# MCU_Net.net
KiCad netlist of a schematic drawn in Altium Designer
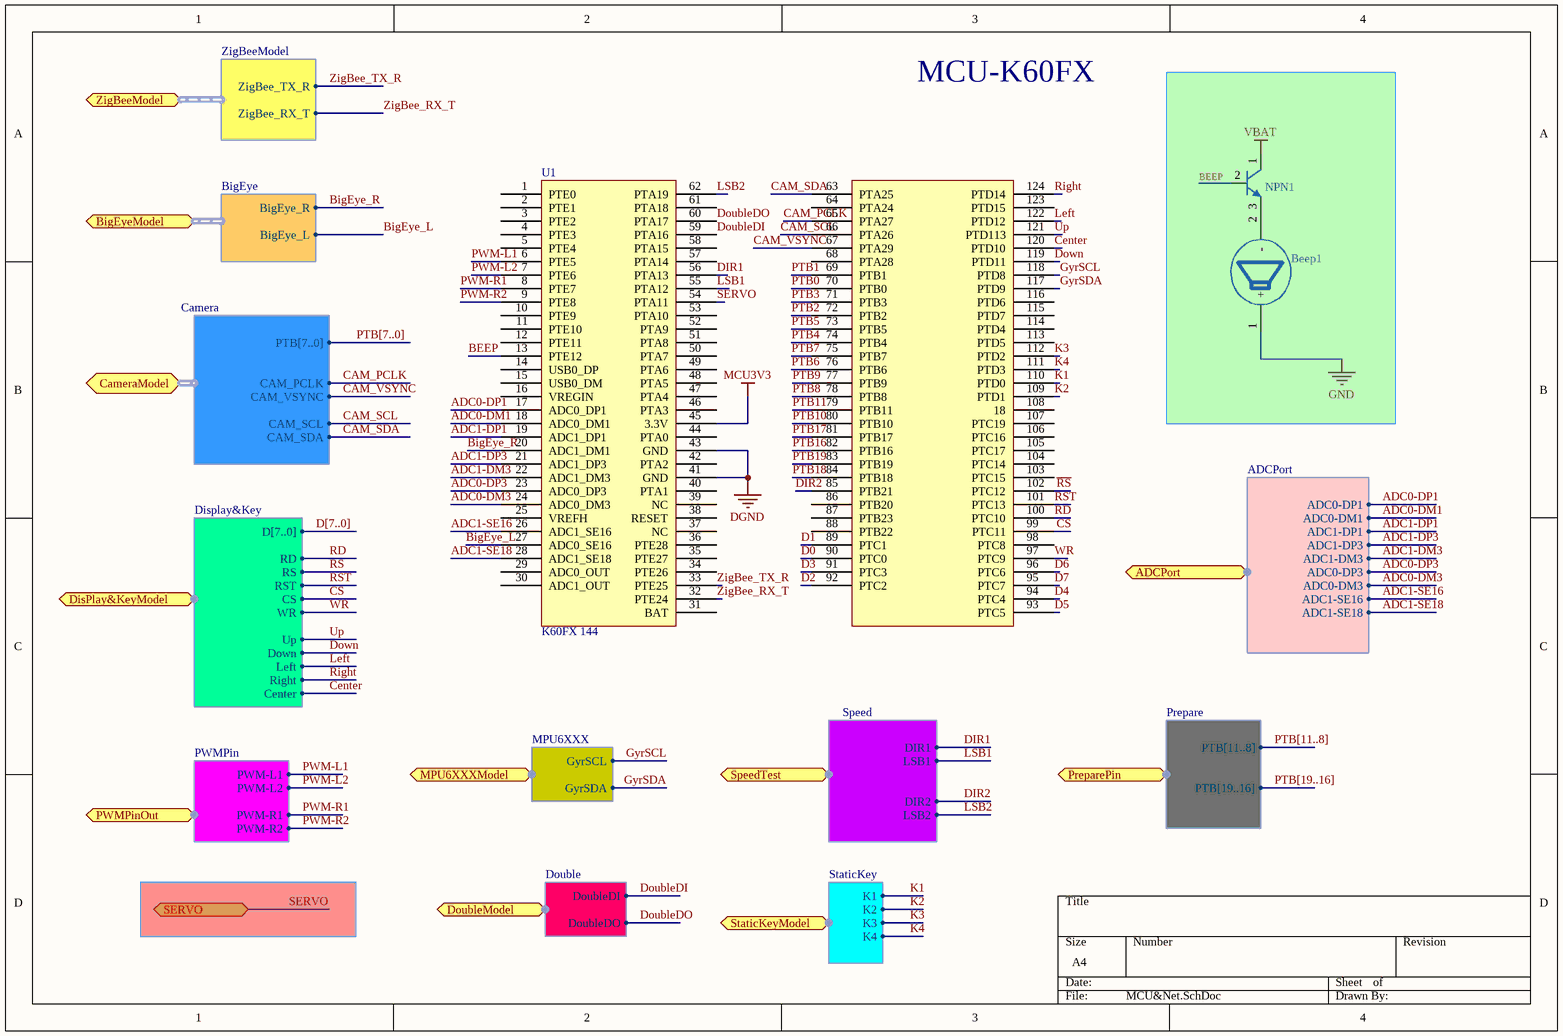
[diagram p0: MCU&Net.SchDoc]

(export (version "E")
  (design (tool "Eeschema 10.0.6"))
  (components
    (comp (ref "Beep1") (value "BEEP") (footprint "BEEP") (libsource (lib "常用原件库") (part "蜂鸣器")))
    (comp (ref "NPN1") (value "NPN") (footprint "三极管  NPN") (libsource (lib "常用原件库") (part "NPN")))
    (comp (ref "U1")
      (value "K60FX 144")
      (footprint "K60FX 144")
      (libsource (lib "常用原件库") (part "K60FX   144"))
    )
  )
  (nets
    (net (code "12") (name "/ADC0-DM1") (class "Default")
      (node (ref "U1") (pin "18") (pinfunction "ADC0_DM1_18") (pintype "passive"))
    )
    (net (code "13") (name "/ADC0-DM3") (class "Default")
      (node (ref "U1") (pin "24") (pinfunction "ADC0_DM3_24") (pintype "passive"))
    )
    (net (code "14") (name "/ADC0-DP1") (class "Default")
      (node (ref "U1") (pin "17") (pinfunction "ADC0_DP1_17") (pintype "passive"))
    )
    (net (code "15") (name "/ADC0-DP3") (class "Default")
      (node (ref "U1") (pin "23") (pinfunction "ADC0_DP3_23") (pintype "passive"))
    )
    (net (code "16") (name "/ADC1-DM3") (class "Default")
      (node (ref "U1") (pin "22") (pinfunction "ADC1_DM3_22") (pintype "passive"))
    )
    (net (code "17") (name "/ADC1-DP1") (class "Default")
      (node (ref "U1") (pin "19") (pinfunction "ADC1_DP1_19") (pintype "passive"))
    )
    (net (code "18") (name "/ADC1-DP3") (class "Default")
      (node (ref "U1") (pin "21") (pinfunction "ADC1_DP3_21") (pintype "passive"))
    )
    (net (code "19") (name "/ADC1-SE16") (class "Default")
      (node (ref "U1") (pin "26") (pinfunction "ADC1_SE16_26") (pintype "passive"))
    )
    (net (code "20") (name "/ADC1-SE18") (class "Default")
      (node (ref "U1") (pin "28") (pinfunction "ADC1_SE18_28") (pintype "passive"))
    )
    (net (code "21") (name "/BEEP") (class "Default")
      (node (ref "NPN1") (pin "2") (pinfunction "2_2") (pintype "passive"))
      (node (ref "U1") (pin "13") (pinfunction "PTE12_13") (pintype "passive"))
    )
    (net (code "22") (name "/BigEye_L") (class "Default")
      (node (ref "U1") (pin "27") (pinfunction "ADC0_SE16_27") (pintype "passive"))
    )
    (net (code "23") (name "/BigEye_R") (class "Default")
      (node (ref "U1") (pin "20") (pinfunction "ADC1_DM1_20") (pintype "passive"))
    )
    (net (code "24") (name "/CAM_PCLK") (class "Default")
      (node (ref "U1") (pin "65") (pinfunction "PTA27_65") (pintype "passive"))
    )
    (net (code "25") (name "/CAM_SCL") (class "Default")
      (node (ref "U1") (pin "66") (pinfunction "PTA26_66") (pintype "passive"))
    )
    (net (code "26") (name "/CAM_SDA") (class "Default")
      (node (ref "U1") (pin "63") (pinfunction "PTA25_63") (pintype "passive"))
    )
    (net (code "27") (name "/CAM_VSYNC") (class "Default")
      (node (ref "U1") (pin "67") (pinfunction "PTA29_67") (pintype "passive"))
    )
    (net (code "28") (name "/CS") (class "Default")
      (node (ref "U1") (pin "99") (pinfunction "PTC11_99") (pintype "passive"))
    )
    (net (code "29") (name "/Center") (class "Default")
      (node (ref "U1") (pin "120") (pinfunction "PTD10_120") (pintype "passive"))
    )
    (net (code "30") (name "/D0") (class "Default")
      (node (ref "U1") (pin "90") (pinfunction "PTC0_90") (pintype "passive"))
    )
    (net (code "31") (name "/D1") (class "Default")
      (node (ref "U1") (pin "89") (pinfunction "PTC1_89") (pintype "passive"))
    )
    (net (code "32") (name "/D2") (class "Default")
      (node (ref "U1") (pin "92") (pinfunction "PTC2_92") (pintype "passive"))
    )
    (net (code "33") (name "/D3") (class "Default")
      (node (ref "U1") (pin "91") (pinfunction "PTC3_91") (pintype "passive"))
    )
    (net (code "34") (name "/D4") (class "Default")
      (node (ref "U1") (pin "94") (pinfunction "PTC4_94") (pintype "passive"))
    )
    (net (code "35") (name "/D5") (class "Default")
      (node (ref "U1") (pin "93") (pinfunction "PTC5_93") (pintype "passive"))
    )
    (net (code "36") (name "/D6") (class "Default")
      (node (ref "U1") (pin "96") (pinfunction "PTC6_96") (pintype "passive"))
    )
    (net (code "37") (name "/D7") (class "Default")
      (node (ref "U1") (pin "95") (pinfunction "PTC7_95") (pintype "passive"))
    )
    (net (code "38") (name "/DIR1") (class "Default")
      (node (ref "U1") (pin "56") (pinfunction "PTA13_56") (pintype "passive"))
    )
    (net (code "39") (name "/DIR2") (class "Default")
      (node (ref "U1") (pin "85") (pinfunction "PTB21_85") (pintype "passive"))
    )
    (net (code "41") (name "/DoubleDI") (class "Default")
      (node (ref "U1") (pin "59") (pinfunction "PTA16_59") (pintype "passive"))
    )
    (net (code "42") (name "/DoubleDO") (class "Default")
      (node (ref "U1") (pin "60") (pinfunction "PTA17_60") (pintype "passive"))
    )
    (net (code "43") (name "/Down") (class "Default")
      (node (ref "U1") (pin "119") (pinfunction "PTD11_119") (pintype "passive"))
    )
    (net (code "44") (name "/GyrSCL") (class "Default")
      (node (ref "U1") (pin "118") (pinfunction "PTD8_118") (pintype "passive"))
    )
    (net (code "45") (name "/GyrSDA") (class "Default")
      (node (ref "U1") (pin "117") (pinfunction "PTD9_117") (pintype "passive"))
    )
    (net (code "46") (name "/K1") (class "Default")
      (node (ref "U1") (pin "110") (pinfunction "PTD0_110") (pintype "passive"))
    )
    (net (code "47") (name "/K2") (class "Default")
      (node (ref "U1") (pin "109") (pinfunction "PTD1_109") (pintype "passive"))
    )
    (net (code "48") (name "/K3") (class "Default")
      (node (ref "U1") (pin "112") (pinfunction "PTD2_112") (pintype "passive"))
    )
    (net (code "49") (name "/K4") (class "Default")
      (node (ref "U1") (pin "111") (pinfunction "PTD3_111") (pintype "passive"))
    )
    (net (code "50") (name "/LSB1") (class "Default")
      (node (ref "U1") (pin "55") (pinfunction "PTA12_55") (pintype "passive"))
    )
    (net (code "51") (name "/LSB2") (class "Default")
      (node (ref "U1") (pin "62") (pinfunction "PTA19_62") (pintype "passive"))
    )
    (net (code "52") (name "/Left") (class "Default")
      (node (ref "U1") (pin "122") (pinfunction "PTD12_122") (pintype "passive"))
    )
    (net (code "53") (name "/PTB0") (class "Default")
      (node (ref "U1") (pin "70") (pinfunction "PTB0_70") (pintype "passive"))
    )
    (net (code "54") (name "/PTB1") (class "Default")
      (node (ref "U1") (pin "69") (pinfunction "PTB1_69") (pintype "passive"))
    )
    (net (code "55") (name "/PTB2") (class "Default")
      (node (ref "U1") (pin "72") (pinfunction "PTB2_72") (pintype "passive"))
    )
    (net (code "56") (name "/PTB3") (class "Default")
      (node (ref "U1") (pin "71") (pinfunction "PTB3_71") (pintype "passive"))
    )
    (net (code "57") (name "/PTB4") (class "Default")
      (node (ref "U1") (pin "74") (pinfunction "PTB4_74") (pintype "passive"))
    )
    (net (code "58") (name "/PTB5") (class "Default")
      (node (ref "U1") (pin "73") (pinfunction "PTB5_73") (pintype "passive"))
    )
    (net (code "59") (name "/PTB6") (class "Default")
      (node (ref "U1") (pin "76") (pinfunction "PTB6_76") (pintype "passive"))
    )
    (net (code "60") (name "/PTB7") (class "Default")
      (node (ref "U1") (pin "75") (pinfunction "PTB7_75") (pintype "passive"))
    )
    (net (code "61") (name "/PTB8") (class "Default")
      (node (ref "U1") (pin "78") (pinfunction "PTB8_78") (pintype "passive"))
    )
    (net (code "62") (name "/PTB9") (class "Default")
      (node (ref "U1") (pin "77") (pinfunction "PTB9_77") (pintype "passive"))
    )
    (net (code "63") (name "/PTB10") (class "Default")
      (node (ref "U1") (pin "80") (pinfunction "PTB10_80") (pintype "passive"))
    )
    (net (code "64") (name "/PTB11") (class "Default")
      (node (ref "U1") (pin "79") (pinfunction "PTB11_79") (pintype "passive"))
    )
    (net (code "65") (name "/PTB16") (class "Default")
      (node (ref "U1") (pin "82") (pinfunction "PTB16_82") (pintype "passive"))
    )
    (net (code "66") (name "/PTB17") (class "Default")
      (node (ref "U1") (pin "81") (pinfunction "PTB17_81") (pintype "passive"))
    )
    (net (code "67") (name "/PTB18") (class "Default")
      (node (ref "U1") (pin "84") (pinfunction "PTB18_84") (pintype "passive"))
    )
    (net (code "68") (name "/PTB19") (class "Default")
      (node (ref "U1") (pin "83") (pinfunction "PTB19_83") (pintype "passive"))
    )
    (net (code "71") (name "/PWM-L1") (class "Default")
      (node (ref "U1") (pin "6") (pinfunction "PTE5_6") (pintype "passive"))
    )
    (net (code "72") (name "/PWM-L2") (class "Default")
      (node (ref "U1") (pin "7") (pinfunction "PTE6_7") (pintype "passive"))
    )
    (net (code "73") (name "/PWM-R1") (class "Default")
      (node (ref "U1") (pin "8") (pinfunction "PTE7_8") (pintype "passive"))
    )
    (net (code "74") (name "/PWM-R2") (class "Default")
      (node (ref "U1") (pin "9") (pinfunction "PTE8_9") (pintype "passive"))
    )
    (net (code "76") (name "/RD") (class "Default")
      (node (ref "U1") (pin "100") (pinfunction "PTC10_100") (pintype "passive"))
    )
    (net (code "77") (name "/RST") (class "Default")
      (node (ref "U1") (pin "101") (pinfunction "PTC13_101") (pintype "passive"))
    )
    (net (code "78") (name "/Right") (class "Default")
      (node (ref "U1") (pin "124") (pinfunction "PTD14_124") (pintype "passive"))
    )
    (net (code "79") (name "/SERVO") (class "Default")
      (node (ref "U1") (pin "54") (pinfunction "PTA11_54") (pintype "passive"))
    )
    (net (code "80") (name "/Up") (class "Default")
      (node (ref "U1") (pin "121") (pinfunction "PTD113_121") (pintype "passive"))
    )
    (net (code "81") (name "/WR") (class "Default")
      (node (ref "U1") (pin "97") (pinfunction "PTC9_97") (pintype "passive"))
    )
    (net (code "82") (name "/ZigBee_RX_T") (class "Default")
      (node (ref "U1") (pin "32") (pinfunction "PTE24_32") (pintype "passive"))
    )
    (net (code "83") (name "/ZigBee_TX_R") (class "Default")
      (node (ref "U1") (pin "33") (pinfunction "PTE25_33") (pintype "passive"))
    )
    (net (code "95") (name "/~{RS}") (class "Default")
      (node (ref "U1") (pin "102") (pinfunction "PTC12_102") (pintype "passive"))
    )
    (net (code "96") (name "DGND") (class "Default")
      (node (ref "U1") (pin "41") (pinfunction "GND_41") (pintype "passive"))
      (node (ref "U1") (pin "43") (pinfunction "GND_43") (pintype "passive"))
    )
    (net (code "97") (name "GND") (class "Default")
      (node (ref "Beep1") (pin "1") (pinfunction "+_1") (pintype "passive"))
    )
    (net (code "98") (name "MCU3V3") (class "Default")
      (node (ref "U1") (pin "45") (pinfunction "3.3V_45") (pintype "passive"))
    )
    (net (code "99") (name "Net-(Beep1--)") (class "Default")
      (node (ref "Beep1") (pin "2") (pinfunction "-_2") (pintype "passive"))
      (node (ref "NPN1") (pin "3") (pinfunction "3_3") (pintype "passive"))
    )
    (net (code "100") (name "VBAT") (class "Default")
      (node (ref "NPN1") (pin "1") (pinfunction "1_1") (pintype "passive"))
    )
    (net (code "101") (name "unconnected-(U1-18-Pad108)") (class "Default")
      (node (ref "U1") (pin "108") (pinfunction "18_108") (pintype "passive"))
    )
    (net (code "102") (name "unconnected-(U1-ADC0_OUT-Pad29)") (class "Default")
      (node (ref "U1") (pin "29") (pinfunction "ADC0_OUT_29") (pintype "passive"))
    )
    (net (code "103") (name "unconnected-(U1-ADC1_OUT-Pad30)") (class "Default")
      (node (ref "U1") (pin "30") (pinfunction "ADC1_OUT_30") (pintype "passive"))
    )
    (net (code "104") (name "unconnected-(U1-BAT-Pad31)") (class "Default")
      (node (ref "U1") (pin "31") (pinfunction "BAT_31") (pintype "passive"))
    )
    (net (code "105") (name "unconnected-(U1-NC-Pad37)") (class "Default")
      (node (ref "U1") (pin "37") (pinfunction "NC_37") (pintype "passive"))
    )
    (net (code "106") (name "unconnected-(U1-NC-Pad39)") (class "Default")
      (node (ref "U1") (pin "39") (pinfunction "NC_39") (pintype "passive"))
    )
    (net (code "107") (name "unconnected-(U1-PTA0-Pad44)") (class "Default")
      (node (ref "U1") (pin "44") (pinfunction "PTA0_44") (pintype "passive"))
    )
    (net (code "108") (name "unconnected-(U1-PTA1-Pad40)") (class "Default")
      (node (ref "U1") (pin "40") (pinfunction "PTA1_40") (pintype "passive"))
    )
    (net (code "109") (name "unconnected-(U1-PTA2-Pad42)") (class "Default")
      (node (ref "U1") (pin "42") (pinfunction "PTA2_42") (pintype "passive"))
    )
    (net (code "110") (name "unconnected-(U1-PTA3-Pad46)") (class "Default")
      (node (ref "U1") (pin "46") (pinfunction "PTA3_46") (pintype "passive"))
    )
    (net (code "111") (name "unconnected-(U1-PTA4-Pad47)") (class "Default")
      (node (ref "U1") (pin "47") (pinfunction "PTA4_47") (pintype "passive"))
    )
    (net (code "112") (name "unconnected-(U1-PTA5-Pad48)") (class "Default")
      (node (ref "U1") (pin "48") (pinfunction "PTA5_48") (pintype "passive"))
    )
    (net (code "113") (name "unconnected-(U1-PTA6-Pad49)") (class "Default")
      (node (ref "U1") (pin "49") (pinfunction "PTA6_49") (pintype "passive"))
    )
    (net (code "114") (name "unconnected-(U1-PTA7-Pad50)") (class "Default")
      (node (ref "U1") (pin "50") (pinfunction "PTA7_50") (pintype "passive"))
    )
    (net (code "115") (name "unconnected-(U1-PTA8-Pad51)") (class "Default")
      (node (ref "U1") (pin "51") (pinfunction "PTA8_51") (pintype "passive"))
    )
    (net (code "116") (name "unconnected-(U1-PTA9-Pad52)") (class "Default")
      (node (ref "U1") (pin "52") (pinfunction "PTA9_52") (pintype "passive"))
    )
    (net (code "117") (name "unconnected-(U1-PTA10-Pad53)") (class "Default")
      (node (ref "U1") (pin "53") (pinfunction "PTA10_53") (pintype "passive"))
    )
    (net (code "118") (name "unconnected-(U1-PTA14-Pad57)") (class "Default")
      (node (ref "U1") (pin "57") (pinfunction "PTA14_57") (pintype "passive"))
    )
    (net (code "119") (name "unconnected-(U1-PTA15-Pad58)") (class "Default")
      (node (ref "U1") (pin "58") (pinfunction "PTA15_58") (pintype "passive"))
    )
    (net (code "120") (name "unconnected-(U1-PTA18-Pad61)") (class "Default")
      (node (ref "U1") (pin "61") (pinfunction "PTA18_61") (pintype "passive"))
    )
    (net (code "121") (name "unconnected-(U1-PTA24-Pad64)") (class "Default")
      (node (ref "U1") (pin "64") (pinfunction "PTA24_64") (pintype "passive"))
    )
    (net (code "122") (name "unconnected-(U1-PTA28-Pad68)") (class "Default")
      (node (ref "U1") (pin "68") (pinfunction "PTA28_68") (pintype "passive"))
    )
    (net (code "123") (name "unconnected-(U1-PTB20-Pad86)") (class "Default")
      (node (ref "U1") (pin "86") (pinfunction "PTB20_86") (pintype "passive"))
    )
    (net (code "124") (name "unconnected-(U1-PTB22-Pad88)") (class "Default")
      (node (ref "U1") (pin "88") (pinfunction "PTB22_88") (pintype "passive"))
    )
    (net (code "125") (name "unconnected-(U1-PTB23-Pad87)") (class "Default")
      (node (ref "U1") (pin "87") (pinfunction "PTB23_87") (pintype "passive"))
    )
    (net (code "126") (name "unconnected-(U1-PTC8-Pad98)") (class "Default")
      (node (ref "U1") (pin "98") (pinfunction "PTC8_98") (pintype "passive"))
    )
    (net (code "127") (name "unconnected-(U1-PTC14-Pad104)") (class "Default")
      (node (ref "U1") (pin "104") (pinfunction "PTC14_104") (pintype "passive"))
    )
    (net (code "128") (name "unconnected-(U1-PTC15-Pad103)") (class "Default")
      (node (ref "U1") (pin "103") (pinfunction "PTC15_103") (pintype "passive"))
    )
    (net (code "129") (name "unconnected-(U1-PTC16-Pad106)") (class "Default")
      (node (ref "U1") (pin "106") (pinfunction "PTC16_106") (pintype "passive"))
    )
    (net (code "130") (name "unconnected-(U1-PTC17-Pad105)") (class "Default")
      (node (ref "U1") (pin "105") (pinfunction "PTC17_105") (pintype "passive"))
    )
    (net (code "131") (name "unconnected-(U1-PTC19-Pad107)") (class "Default")
      (node (ref "U1") (pin "107") (pinfunction "PTC19_107") (pintype "passive"))
    )
    (net (code "132") (name "unconnected-(U1-PTD4-Pad114)") (class "Default")
      (node (ref "U1") (pin "114") (pinfunction "PTD4_114") (pintype "passive"))
    )
    (net (code "133") (name "unconnected-(U1-PTD5-Pad113)") (class "Default")
      (node (ref "U1") (pin "113") (pinfunction "PTD5_113") (pintype "passive"))
    )
    (net (code "134") (name "unconnected-(U1-PTD6-Pad116)") (class "Default")
      (node (ref "U1") (pin "116") (pinfunction "PTD6_116") (pintype "passive"))
    )
    (net (code "135") (name "unconnected-(U1-PTD7-Pad115)") (class "Default")
      (node (ref "U1") (pin "115") (pinfunction "PTD7_115") (pintype "passive"))
    )
    (net (code "136") (name "unconnected-(U1-PTD15-Pad123)") (class "Default")
      (node (ref "U1") (pin "123") (pinfunction "PTD15_123") (pintype "passive"))
    )
    (net (code "137") (name "unconnected-(U1-PTE0-Pad1)") (class "Default")
      (node (ref "U1") (pin "1") (pinfunction "PTE0_1") (pintype "passive"))
    )
    (net (code "138") (name "unconnected-(U1-PTE1-Pad2)") (class "Default")
      (node (ref "U1") (pin "2") (pinfunction "PTE1_2") (pintype "passive"))
    )
    (net (code "139") (name "unconnected-(U1-PTE2-Pad3)") (class "Default")
      (node (ref "U1") (pin "3") (pinfunction "PTE2_3") (pintype "passive"))
    )
    (net (code "140") (name "unconnected-(U1-PTE3-Pad4)") (class "Default")
      (node (ref "U1") (pin "4") (pinfunction "PTE3_4") (pintype "passive"))
    )
    (net (code "141") (name "unconnected-(U1-PTE4-Pad5)") (class "Default")
      (node (ref "U1") (pin "5") (pinfunction "PTE4_5") (pintype "passive"))
    )
    (net (code "142") (name "unconnected-(U1-PTE9-Pad10)") (class "Default")
      (node (ref "U1") (pin "10") (pinfunction "PTE9_10") (pintype "passive"))
    )
    (net (code "143") (name "unconnected-(U1-PTE10-Pad11)") (class "Default")
      (node (ref "U1") (pin "11") (pinfunction "PTE10_11") (pintype "passive"))
    )
    (net (code "144") (name "unconnected-(U1-PTE11-Pad12)") (class "Default")
      (node (ref "U1") (pin "12") (pinfunction "PTE11_12") (pintype "passive"))
    )
    (net (code "145") (name "unconnected-(U1-PTE26-Pad34)") (class "Default")
      (node (ref "U1") (pin "34") (pinfunction "PTE26_34") (pintype "passive"))
    )
    (net (code "146") (name "unconnected-(U1-PTE27-Pad35)") (class "Default")
      (node (ref "U1") (pin "35") (pinfunction "PTE27_35") (pintype "passive"))
    )
    (net (code "147") (name "unconnected-(U1-PTE28-Pad36)") (class "Default")
      (node (ref "U1") (pin "36") (pinfunction "PTE28_36") (pintype "passive"))
    )
    (net (code "148") (name "unconnected-(U1-RESET-Pad38)") (class "Default")
      (node (ref "U1") (pin "38") (pinfunction "RESET_38") (pintype "passive"))
    )
    (net (code "149") (name "unconnected-(U1-USB0_DM-Pad15)") (class "Default")
      (node (ref "U1") (pin "15") (pinfunction "USB0_DM_15") (pintype "passive"))
    )
    (net (code "150") (name "unconnected-(U1-USB0_DP-Pad14)") (class "Default")
      (node (ref "U1") (pin "14") (pinfunction "USB0_DP_14") (pintype "passive"))
    )
    (net (code "151") (name "unconnected-(U1-VREFH-Pad25)") (class "Default")
      (node (ref "U1") (pin "25") (pinfunction "VREFH_25") (pintype "passive"))
    )
    (net (code "152") (name "unconnected-(U1-VREGIN-Pad16)") (class "Default")
      (node (ref "U1") (pin "16") (pinfunction "VREGIN_16") (pintype "passive"))
    )
  )
)
